# MainBoard.net
KiCad netlist of a schematic drawn in Altium Designer
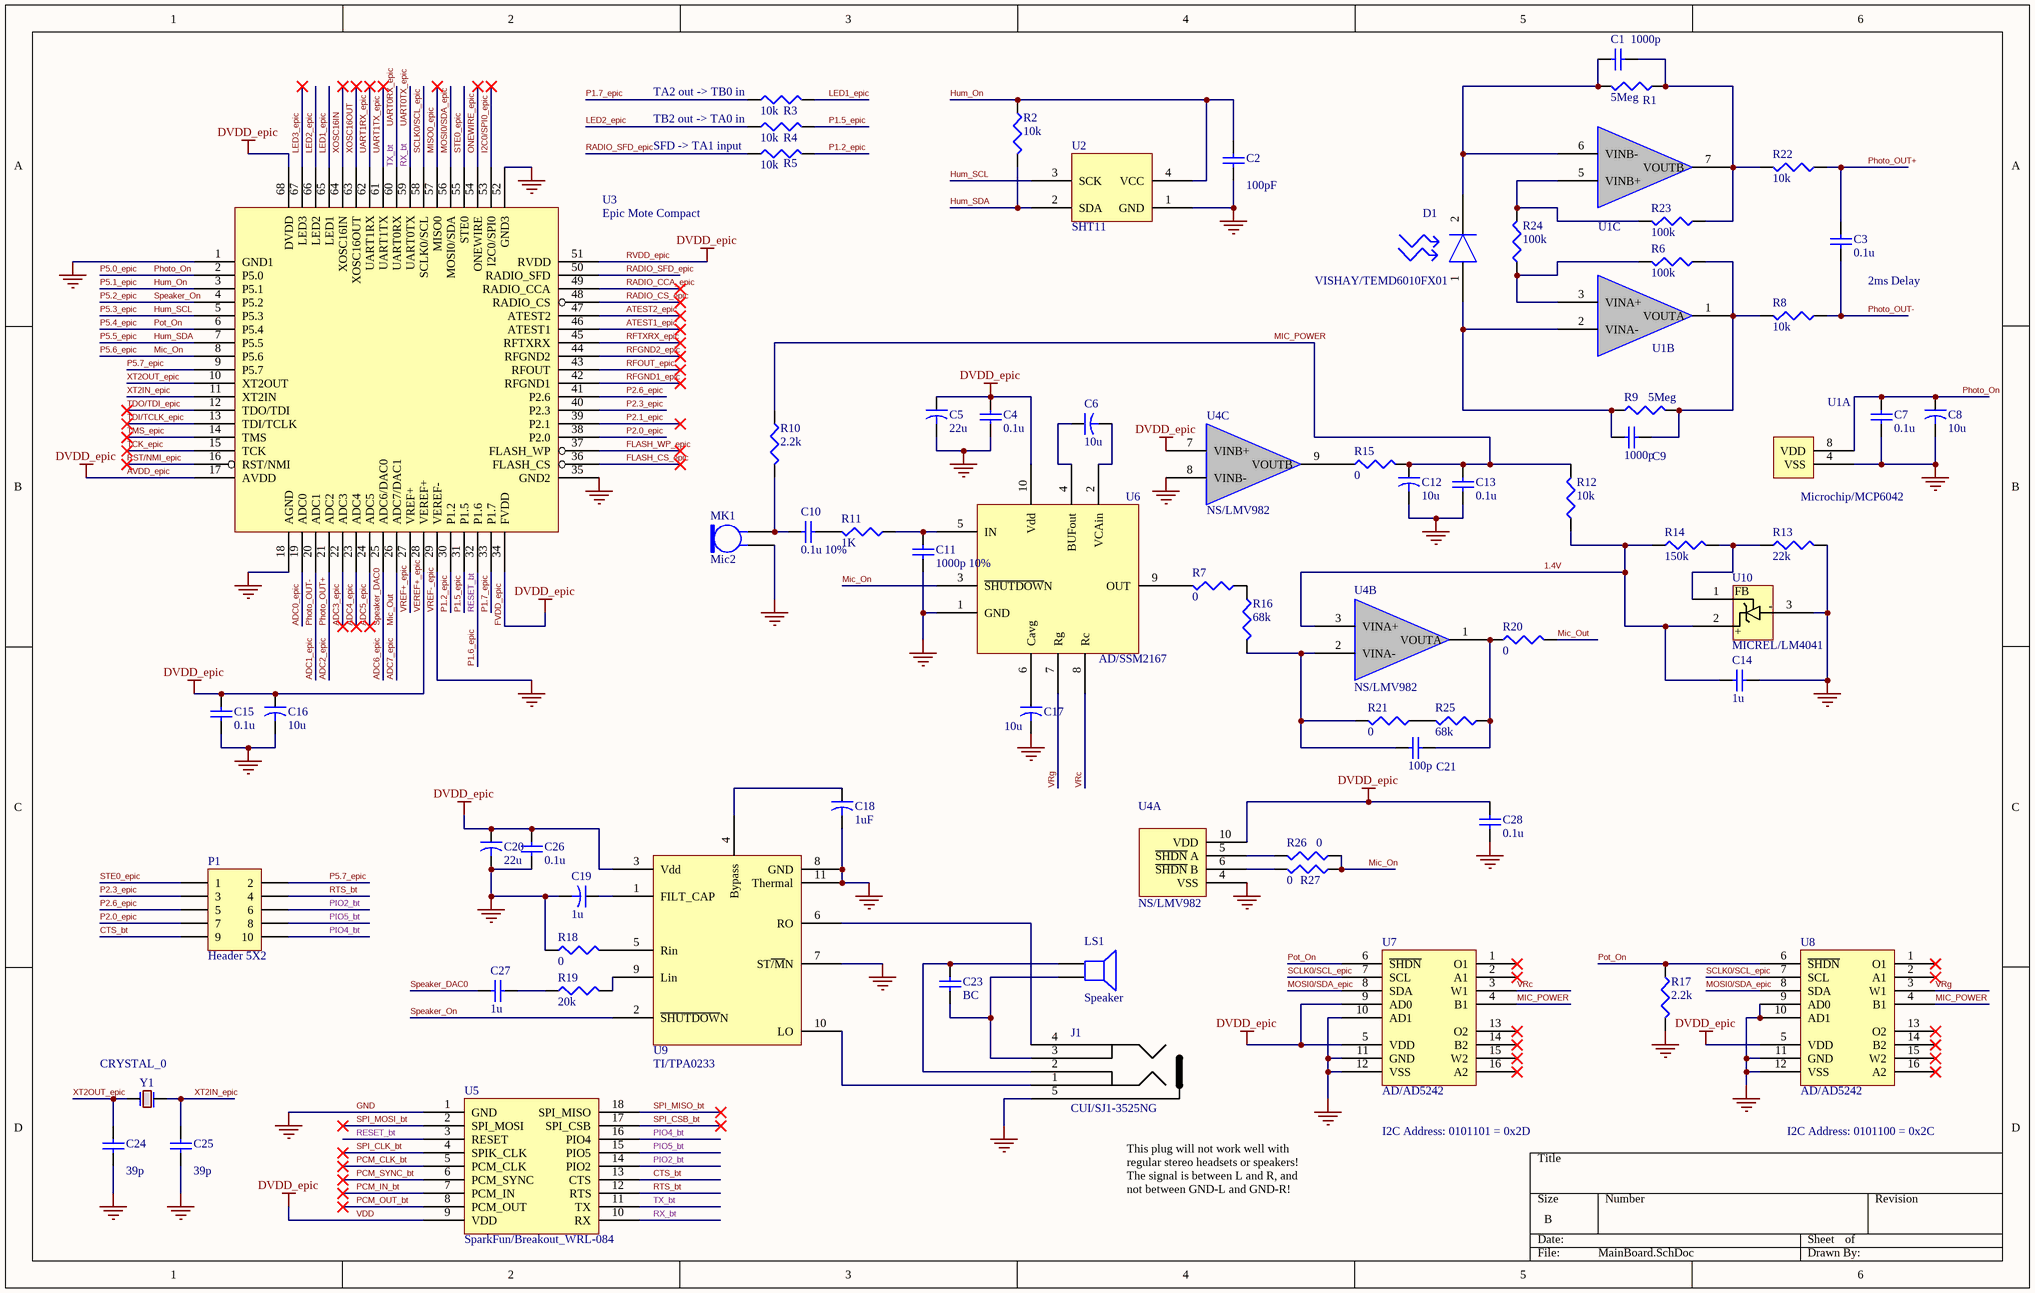
[diagram p0: MainBoard.SchDoc]

(export (version "E")
  (design (tool "Eeschema 10.0.6"))
  (components
    (comp (ref "C1")
      (value "1000p")
      (footprint "CC1608-0603")
      (description "Capacitor")
      (fields (field (name "Comment") "Cap") (field (name "PUBLISHER") "Altium Limited"))
      (libsource (lib "Miscellaneous Devices") (part "Cap"))
    )
    (comp (ref "C2")
      (value "100pF")
      (footprint "CC1608-0603")
      (description "Capacitor")
      (fields (field (name "Comment") "Cap") (field (name "PUBLISHER") "Altium Limited"))
      (libsource (lib "Miscellaneous Devices") (part "Cap"))
    )
    (comp (ref "C3")
      (value "0.1u")
      (footprint "CC1608-0603")
      (description "Capacitor")
      (fields (field (name "Comment") "Cap") (field (name "PUBLISHER") "Altium Limited"))
      (libsource (lib "Miscellaneous Devices") (part "Cap"))
    )
    (comp (ref "C4")
      (value "0.1u")
      (footprint "CC1608-0603")
      (description "Capacitor")
      (fields (field (name "Comment") "Cap") (field (name "PUBLISHER") "Altium Limited"))
      (libsource (lib "Miscellaneous Devices") (part "Cap"))
    )
    (comp (ref "C5")
      (value "22u")
      (footprint "CC3216-1206")
      (description "Capacitor")
      (fields (field (name "Comment") "Cap2") (field (name "PUBLISHER") "Altium Limited"))
      (libsource (lib "") (part "Cap2_1"))
    )
    (comp (ref "C6")
      (value "10u")
      (footprint "CC1608-0603")
      (description "Capacitor")
      (fields (field (name "Comment") "Cap2") (field (name "PUBLISHER") "Altium Limited"))
      (libsource (lib "Miscellaneous Devices") (part "Cap2"))
    )
    (comp (ref "C7")
      (value "0.1u")
      (footprint "CC1608-0603")
      (description "Capacitor")
      (fields (field (name "Comment") "Cap") (field (name "PUBLISHER") "Altium Limited"))
      (libsource (lib "Miscellaneous Devices") (part "Cap"))
    )
    (comp (ref "C8")
      (value "10u")
      (footprint "CC1608-0603")
      (description "Capacitor")
      (fields (field (name "Comment") "Cap2") (field (name "PUBLISHER") "Altium Limited"))
      (libsource (lib "") (part "Cap2_1"))
    )
    (comp (ref "C9")
      (value "1000p")
      (footprint "CC1608-0603")
      (description "Capacitor")
      (fields (field (name "Comment") "Cap") (field (name "PUBLISHER") "Altium Limited"))
      (libsource (lib "Miscellaneous Devices") (part "Cap"))
    )
    (comp (ref "C10")
      (value "0.1u 10%")
      (footprint "CC1608-0603")
      (description "Capacitor")
      (fields (field (name "Comment") "Cap") (field (name "PUBLISHER") "Altium Limited"))
      (libsource (lib "Miscellaneous Devices") (part "Cap"))
    )
    (comp (ref "C11")
      (value "1000p 10%")
      (footprint "CC1608-0603")
      (description "Capacitor")
      (fields (field (name "Comment") "Cap") (field (name "PUBLISHER") "Altium Limited"))
      (libsource (lib "Miscellaneous Devices") (part "Cap"))
    )
    (comp (ref "C12")
      (value "10u")
      (footprint "CC1608-0603")
      (description "Capacitor")
      (fields (field (name "Comment") "Cap2") (field (name "PUBLISHER") "Altium Limited"))
      (libsource (lib "") (part "Cap2_1"))
    )
    (comp (ref "C13")
      (value "0.1u")
      (footprint "CC1608-0603")
      (description "Capacitor")
      (fields (field (name "Comment") "Cap") (field (name "PUBLISHER") "Altium Limited"))
      (libsource (lib "Miscellaneous Devices") (part "Cap"))
    )
    (comp (ref "C14")
      (value "1u")
      (footprint "CC1608-0603")
      (description "Capacitor")
      (fields (field (name "Comment") "Cap") (field (name "PUBLISHER") "Altium Limited"))
      (libsource (lib "") (part "Cap_1"))
    )
    (comp (ref "C15")
      (value "0.1u")
      (footprint "CC1608-0603")
      (description "Capacitor")
      (fields (field (name "Comment") "Cap") (field (name "PUBLISHER") "Altium Limited"))
      (libsource (lib "Miscellaneous Devices") (part "Cap"))
    )
    (comp (ref "C16")
      (value "10u")
      (footprint "CC1608-0603")
      (description "Capacitor")
      (fields (field (name "Comment") "Cap2") (field (name "PUBLISHER") "Altium Limited"))
      (libsource (lib "") (part "Cap2_1"))
    )
    (comp (ref "C17")
      (value "10u")
      (footprint "CC1608-0603")
      (description "Capacitor")
      (fields (field (name "Comment") "Cap2") (field (name "PUBLISHER") "Altium Limited"))
      (libsource (lib "Miscellaneous Devices") (part "Cap2"))
    )
    (comp (ref "C18")
      (value "1uF")
      (footprint "CC1608-0603")
      (description "Capacitor")
      (fields (field (name "Comment") "Cap2") (field (name "PUBLISHER") "Altium Limited"))
      (libsource (lib "Miscellaneous Devices") (part "Cap2"))
    )
    (comp (ref "C19")
      (value "1u")
      (footprint "CC1608-0603")
      (description "Capacitor")
      (fields (field (name "Comment") "Cap2") (field (name "PUBLISHER") "Altium Limited"))
      (libsource (lib "Miscellaneous Devices") (part "Cap2"))
    )
    (comp (ref "C20")
      (value "22u")
      (footprint "CC3216-1206")
      (description "Capacitor")
      (fields (field (name "Comment") "Cap2") (field (name "PUBLISHER") "Altium Limited"))
      (libsource (lib "") (part "Cap2_1"))
    )
    (comp (ref "C21")
      (value "100p")
      (footprint "CC1608-0603")
      (description "Capacitor")
      (fields (field (name "Comment") "Cap") (field (name "PUBLISHER") "Altium Limited"))
      (libsource (lib "Miscellaneous Devices") (part "Cap"))
    )
    (comp (ref "C23")
      (value "BC")
      (footprint "CC1608-0603")
      (description "Capacitor")
      (fields (field (name "Comment") "Cap") (field (name "PUBLISHER") "Altium Limited"))
      (libsource (lib "Miscellaneous Devices") (part "Cap"))
    )
    (comp (ref "C24")
      (value "39p")
      (footprint "CC1608-0603")
      (description "Capacitor")
      (fields (field (name "Comment") "Cap") (field (name "PUBLISHER") "Altium Limited"))
      (libsource (lib "Miscellaneous Devices") (part "Cap"))
    )
    (comp (ref "C25")
      (value "39p")
      (footprint "CC1608-0603")
      (description "Capacitor")
      (fields (field (name "Comment") "Cap") (field (name "PUBLISHER") "Altium Limited"))
      (libsource (lib "Miscellaneous Devices") (part "Cap"))
    )
    (comp (ref "C26")
      (value "0.1u")
      (footprint "CC1608-0603")
      (description "Capacitor")
      (fields (field (name "Comment") "Cap") (field (name "PUBLISHER") "Altium Limited"))
      (libsource (lib "Miscellaneous Devices") (part "Cap"))
    )
    (comp (ref "C27")
      (value "1u")
      (footprint "CC1608-0603")
      (description "Capacitor")
      (fields (field (name "Comment") "Cap") (field (name "PUBLISHER") "Altium Limited"))
      (libsource (lib "Miscellaneous Devices") (part "Cap"))
    )
    (comp (ref "C28")
      (value "0.1u")
      (footprint "CC1608-0603")
      (description "Capacitor")
      (fields (field (name "Comment") "Cap") (field (name "PUBLISHER") "Altium Limited"))
      (libsource (lib "Miscellaneous Devices") (part "Cap"))
    )
    (comp (ref "D1")
      (value "VISHAY/TEMD6010FX01")
      (footprint "VISHAY/TEMD6010FX01")
      (libsource (lib "Schematics") (part "VISHAY/TEMD6010FX01"))
    )
    (comp (ref "J1")
      (value "CUI/SJ1-3525NG")
      (footprint "CUI/PHONE_JACK_3.5mm")
      (libsource (lib "Schematics") (part "CUI/SJ1-3525NG"))
    )
    (comp (ref "LS1")
      (value "Speaker")
      (footprint "PIN2")
      (description "Loudspeaker")
      (fields (field (name "PUBLISHER") "Altium Limited"))
      (libsource (lib "Miscellaneous Devices") (part "Speaker"))
    )
    (comp (ref "MK1")
      (value "Mic2")
      (footprint "PIN2")
      (description "Microphone")
      (fields (field (name "PUBLISHER") "Altium Limited"))
      (libsource (lib "Miscellaneous Devices") (part "Mic2"))
    )
    (comp (ref "P1")
      (value "Header 5X2")
      (footprint "HDR2X5")
      (description "Header, 5-Pin, Dual row")
      (fields (field (name "PUBLISHER") "Altium Limited"))
      (libsource (lib "Miscellaneous Connectors") (part "Header 5X2"))
    )
    (comp (ref "R1")
      (value "5Meg")
      (footprint "CR1608-0603")
      (description "Resistor")
      (fields (field (name "Comment") "Res3") (field (name "PUBLISHER") "Altium Limited"))
      (libsource (lib "Miscellaneous Devices") (part "Res3"))
    )
    (comp (ref "R2")
      (value "10k")
      (footprint "CR1608-0603")
      (description "Resistor")
      (fields (field (name "Comment") "Res3") (field (name "PUBLISHER") "Altium Limited"))
      (libsource (lib "Miscellaneous Devices") (part "Res3"))
    )
    (comp (ref "R3")
      (value "10k")
      (footprint "CR1608-0603")
      (description "Resistor")
      (fields (field (name "Comment") "Res3") (field (name "PUBLISHER") "Altium Limited"))
      (libsource (lib "Miscellaneous Devices") (part "Res3"))
    )
    (comp (ref "R4")
      (value "10k")
      (footprint "CR1608-0603")
      (description "Resistor")
      (fields (field (name "Comment") "Res3") (field (name "PUBLISHER") "Altium Limited"))
      (libsource (lib "Miscellaneous Devices") (part "Res3"))
    )
    (comp (ref "R5")
      (value "10k")
      (footprint "CR1608-0603")
      (description "Resistor")
      (fields (field (name "Comment") "Res3") (field (name "PUBLISHER") "Altium Limited"))
      (libsource (lib "Miscellaneous Devices") (part "Res3"))
    )
    (comp (ref "R6")
      (value "100k")
      (footprint "CR1608-0603")
      (description "Resistor")
      (fields (field (name "Comment") "Res3") (field (name "PUBLISHER") "Altium Limited"))
      (libsource (lib "Miscellaneous Devices") (part "Res3"))
    )
    (comp (ref "R7")
      (value "0")
      (footprint "CR1608-0603")
      (description "Resistor")
      (fields (field (name "Comment") "Res3") (field (name "PUBLISHER") "Altium Limited"))
      (libsource (lib "Miscellaneous Devices") (part "Res3"))
    )
    (comp (ref "R8")
      (value "10k")
      (footprint "CR1608-0603")
      (description "Resistor")
      (fields (field (name "Comment") "Res3") (field (name "PUBLISHER") "Altium Limited"))
      (libsource (lib "Miscellaneous Devices") (part "Res3"))
    )
    (comp (ref "R9")
      (value "5Meg")
      (footprint "CR1608-0603")
      (description "Resistor")
      (fields (field (name "Comment") "Res3") (field (name "PUBLISHER") "Altium Limited"))
      (libsource (lib "Miscellaneous Devices") (part "Res3"))
    )
    (comp (ref "R10")
      (value "2.2k")
      (footprint "CR1608-0603")
      (description "Resistor")
      (fields (field (name "Comment") "Res3") (field (name "PUBLISHER") "Altium Limited"))
      (libsource (lib "Miscellaneous Devices") (part "Res3"))
    )
    (comp (ref "R11")
      (value "1K")
      (footprint "CR1608-0603")
      (description "Resistor")
      (fields (field (name "Comment") "Res3") (field (name "PUBLISHER") "Altium Limited"))
      (libsource (lib "Miscellaneous Devices") (part "Res3"))
    )
    (comp (ref "R12")
      (value "10k")
      (footprint "CR1608-0603")
      (description "Resistor")
      (fields (field (name "Comment") "Res3") (field (name "PUBLISHER") "Altium Limited"))
      (libsource (lib "Miscellaneous Devices") (part "Res3"))
    )
    (comp (ref "R13")
      (value "22k")
      (footprint "CR1608-0603")
      (description "Resistor")
      (fields (field (name "Comment") "Res3") (field (name "PUBLISHER") "Altium Limited"))
      (libsource (lib "Miscellaneous Devices") (part "Res3"))
    )
    (comp (ref "R14")
      (value "150k")
      (footprint "CR1608-0603")
      (description "Resistor")
      (fields (field (name "Comment") "Res3") (field (name "PUBLISHER") "Altium Limited"))
      (libsource (lib "Miscellaneous Devices") (part "Res3"))
    )
    (comp (ref "R15")
      (value "0")
      (footprint "CR1608-0603")
      (description "Resistor")
      (fields (field (name "Comment") "Res3") (field (name "PUBLISHER") "Altium Limited"))
      (libsource (lib "Miscellaneous Devices") (part "Res3"))
    )
    (comp (ref "R16")
      (value "68k")
      (footprint "CR1608-0603")
      (description "Resistor")
      (fields (field (name "Comment") "Res3") (field (name "PUBLISHER") "Altium Limited"))
      (libsource (lib "") (part "Res3_1"))
    )
    (comp (ref "R17")
      (value "2.2k")
      (footprint "CR1608-0603")
      (description "Resistor")
      (fields (field (name "Comment") "Res3") (field (name "PUBLISHER") "Altium Limited"))
      (libsource (lib "Miscellaneous Devices") (part "Res3"))
    )
    (comp (ref "R18")
      (value "0")
      (footprint "CR1608-0603")
      (description "Resistor")
      (fields (field (name "Comment") "Res3") (field (name "PUBLISHER") "Altium Limited"))
      (libsource (lib "Miscellaneous Devices") (part "Res3"))
    )
    (comp (ref "R19")
      (value "20k")
      (footprint "CR1608-0603")
      (description "Resistor")
      (fields (field (name "Comment") "Res3") (field (name "PUBLISHER") "Altium Limited"))
      (libsource (lib "Miscellaneous Devices") (part "Res3"))
    )
    (comp (ref "R20")
      (value "0")
      (footprint "CR1608-0603")
      (description "Resistor")
      (fields (field (name "Comment") "Res3") (field (name "PUBLISHER") "Altium Limited"))
      (libsource (lib "Miscellaneous Devices") (part "Res3"))
    )
    (comp (ref "R21")
      (value "0")
      (footprint "CR1608-0603")
      (description "Resistor")
      (fields (field (name "Comment") "Res3") (field (name "PUBLISHER") "Altium Limited"))
      (libsource (lib "Miscellaneous Devices") (part "Res3"))
    )
    (comp (ref "R22")
      (value "10k")
      (footprint "CR1608-0603")
      (description "Resistor")
      (fields (field (name "Comment") "Res3") (field (name "PUBLISHER") "Altium Limited"))
      (libsource (lib "Miscellaneous Devices") (part "Res3"))
    )
    (comp (ref "R23")
      (value "100k")
      (footprint "CR1608-0603")
      (description "Resistor")
      (fields (field (name "Comment") "Res3") (field (name "PUBLISHER") "Altium Limited"))
      (libsource (lib "Miscellaneous Devices") (part "Res3"))
    )
    (comp (ref "R24")
      (value "100k")
      (footprint "CR1608-0603")
      (description "Resistor")
      (fields (field (name "Comment") "Res3") (field (name "PUBLISHER") "Altium Limited"))
      (libsource (lib "Miscellaneous Devices") (part "Res3"))
    )
    (comp (ref "R25")
      (value "68k")
      (footprint "CR1608-0603")
      (description "Resistor")
      (fields (field (name "Comment") "Res3") (field (name "PUBLISHER") "Altium Limited"))
      (libsource (lib "Miscellaneous Devices") (part "Res3"))
    )
    (comp (ref "R26")
      (value "0")
      (footprint "CR1608-0603")
      (description "Resistor")
      (fields (field (name "Comment") "Res3") (field (name "PUBLISHER") "Altium Limited"))
      (libsource (lib "Miscellaneous Devices") (part "Res3"))
    )
    (comp (ref "R27")
      (value "0")
      (footprint "CR1608-0603")
      (description "Resistor")
      (fields (field (name "Comment") "Res3") (field (name "PUBLISHER") "Altium Limited"))
      (libsource (lib "Miscellaneous Devices") (part "Res3"))
    )
    (comp (ref "U1")
      (value "Microchip/MCP6042")
      (footprint "SOIC127P600X175-8N")
      (libsource (lib "Schematics") (part "Microchip/MCP6042"))
    )
    (comp (ref "U2")
      (value "SHT11")
      (footprint "Sensirion/SHT11")
      (libsource (lib "Schematics") (part "SHT11"))
    )
    (comp (ref "U3")
      (value "Epic Mote Compact")
      (footprint "UCB/Epic_Quanto_Header")
      (libsource (lib "Schematics") (part "Epic Mote Compact"))
    )
    (comp (ref "U4")
      (value "NS/LMV982")
      (footprint "MSOP10")
      (libsource (lib "Schematics") (part "NS/LMV982"))
    )
    (comp (ref "U5")
      (value "SparkFun/Breakout_WRL-084")
      (footprint "SparkFun/Breakout_WRL-084")
      (libsource (lib "Schematics") (part "SparkFun/Breakout_WRL-084"))
    )
    (comp (ref "U6")
      (value "AD/SSM2167")
      (footprint "MSOP127P600-8N")
      (libsource (lib "Schematics") (part "AD/SSM2167"))
    )
    (comp (ref "U7")
      (value "AD/AD5242")
      (footprint "SOIC127P600X175-16N")
      (libsource (lib "Schematics") (part "AD/AD5242"))
    )
    (comp (ref "U8")
      (value "AD/AD5242")
      (footprint "SOIC127P600X175-16N")
      (libsource (lib "Schematics") (part "AD/AD5242"))
    )
    (comp (ref "U9")
      (value "TI/TPA0233")
      (footprint "TSSOP50P480X107_HS-10N")
      (libsource (lib "Schematics") (part "TI/TPA0233"))
    )
    (comp (ref "U10")
      (value "MICREL/LM4041")
      (footprint "SOT231 (M3)")
      (libsource (lib "Schematics") (part "MICREL/LM4041"))
    )
    (comp (ref "Y1")
      (value "CRYSTAL_0")
      (footprint "ECS/CSM-7SSX")
      (libsource (lib "Schematics") (part "CRYSTAL_0"))
    )
  )
  (nets
    (net (code "1") (name "/1.4V") (class "Default")
      (node (ref "C14") (pin "1") (pinfunction "1_1") (pintype "passive"))
      (node (ref "R12") (pin "1") (pinfunction "1_1") (pintype "passive"))
      (node (ref "R14") (pin "1") (pinfunction "1_1") (pintype "passive"))
      (node (ref "U10") (pin "2") (pinfunction "2_2") (pintype "passive"))
      (node (ref "U4") (pin "3") (pinfunction "VINA+_3") (pintype "passive"))
    )
    (net (code "2") (name "/ADC0_epic") (class "Default")
      (node (ref "U3") (pin "19") (pinfunction "ADC0_19") (pintype "passive"))
    )
    (net (code "3") (name "/ADC1_epic") (class "Default")
      (node (ref "C3") (pin "2") (pinfunction "2_2") (pintype "passive"))
      (node (ref "R8") (pin "1") (pinfunction "1_1") (pintype "passive"))
      (node (ref "U3") (pin "20") (pinfunction "ADC1_20") (pintype "passive"))
    )
    (net (code "4") (name "/ADC2_epic") (class "Default")
      (node (ref "C3") (pin "1") (pinfunction "1_1") (pintype "passive"))
      (node (ref "R22") (pin "1") (pinfunction "1_1") (pintype "passive"))
      (node (ref "U3") (pin "21") (pinfunction "ADC2_21") (pintype "passive"))
    )
    (net (code "5") (name "/ADC3_epic") (class "Default")
      (node (ref "U3") (pin "22") (pinfunction "ADC3_22") (pintype "passive+no_connect"))
    )
    (net (code "6") (name "/ADC4_epic") (class "Default")
      (node (ref "U3") (pin "23") (pinfunction "ADC4_23") (pintype "passive+no_connect"))
    )
    (net (code "7") (name "/ADC5_epic") (class "Default")
      (node (ref "U3") (pin "24") (pinfunction "ADC5_24") (pintype "passive+no_connect"))
    )
    (net (code "8") (name "/ADC6_epic") (class "Default")
      (node (ref "C27") (pin "2") (pinfunction "2_2") (pintype "passive"))
      (node (ref "U3") (pin "25") (pinfunction "ADC6/DAC0_25") (pintype "passive"))
    )
    (net (code "9") (name "/ADC7_epic") (class "Default")
      (node (ref "R20") (pin "2") (pinfunction "2_2") (pintype "passive"))
      (node (ref "U3") (pin "26") (pinfunction "ADC7/DAC1_26") (pintype "passive"))
    )
    (net (code "10") (name "/ATEST1_epic") (class "Default")
      (node (ref "U3") (pin "46") (pinfunction "ATEST1_46") (pintype "passive+no_connect"))
    )
    (net (code "11") (name "/ATEST2_epic") (class "Default")
      (node (ref "U3") (pin "47") (pinfunction "ATEST2_47") (pintype "passive+no_connect"))
    )
    (net (code "12") (name "/CTS_bt") (class "Default")
      (node (ref "P1") (pin "9") (pinfunction "9_9") (pintype "passive"))
      (node (ref "U5") (pin "13") (pinfunction "CTS_13") (pintype "passive"))
    )
    (net (code "13") (name "/FLASH_CS_epic") (class "Default")
      (node (ref "U3") (pin "36") (pinfunction "FLASH_CS_36") (pintype "passive+no_connect"))
    )
    (net (code "14") (name "/FLASH_WP_epic") (class "Default")
      (node (ref "U3") (pin "37") (pinfunction "FLASH_WP_37") (pintype "passive+no_connect"))
    )
    (net (code "15") (name "/Hum_On") (class "Default")
      (node (ref "C2") (pin "2") (pinfunction "2_2") (pintype "passive"))
      (node (ref "R2") (pin "1") (pinfunction "1_1") (pintype "passive"))
      (node (ref "U2") (pin "4") (pinfunction "VCC_4") (pintype "power_in"))
      (node (ref "U3") (pin "3") (pinfunction "P5.1_3") (pintype "passive"))
    )
    (net (code "16") (name "/Hum_SCL") (class "Default")
      (node (ref "U2") (pin "3") (pinfunction "SCK_3") (pintype "passive"))
      (node (ref "U3") (pin "5") (pinfunction "P5.3_5") (pintype "passive"))
    )
    (net (code "17") (name "/Hum_SDA") (class "Default")
      (node (ref "R2") (pin "2") (pinfunction "2_2") (pintype "passive"))
      (node (ref "U2") (pin "2") (pinfunction "SDA_2") (pintype "passive"))
      (node (ref "U3") (pin "7") (pinfunction "P5.5_7") (pintype "passive"))
    )
    (net (code "18") (name "/I2C0{slash}SPI0_epic") (class "Default")
      (node (ref "U3") (pin "53") (pinfunction "I2C0/SPI0_53") (pintype "passive+no_connect"))
    )
    (net (code "19") (name "/LED1_epic") (class "Default")
      (node (ref "R3") (pin "2") (pinfunction "2_2") (pintype "passive"))
      (node (ref "U3") (pin "65") (pinfunction "LED1_65") (pintype "passive"))
    )
    (net (code "20") (name "/LED2_epic") (class "Default")
      (node (ref "R4") (pin "1") (pinfunction "1_1") (pintype "passive"))
      (node (ref "U3") (pin "66") (pinfunction "LED2_66") (pintype "passive"))
    )
    (net (code "21") (name "/LED3_epic") (class "Default")
      (node (ref "U3") (pin "67") (pinfunction "LED3_67") (pintype "passive+no_connect"))
    )
    (net (code "22") (name "/MIC_POWER") (class "Default")
      (node (ref "C12") (pin "1") (pinfunction "1_1") (pintype "passive"))
      (node (ref "C13") (pin "1") (pinfunction "1_1") (pintype "passive"))
      (node (ref "R10") (pin "1") (pinfunction "1_1") (pintype "passive"))
      (node (ref "R12") (pin "2") (pinfunction "2_2") (pintype "passive"))
      (node (ref "R15") (pin "2") (pinfunction "2_2") (pintype "passive"))
      (node (ref "U7") (pin "4") (pinfunction "B1_4") (pintype "passive"))
      (node (ref "U8") (pin "4") (pinfunction "B1_4") (pintype "passive"))
    )
    (net (code "23") (name "/MISO0_epic") (class "Default")
      (node (ref "U3") (pin "57") (pinfunction "MISO0_57") (pintype "passive+no_connect"))
    )
    (net (code "24") (name "/MOSI0{slash}SDA_epic") (class "Default")
      (node (ref "U3") (pin "56") (pinfunction "MOSI0/SDA_56") (pintype "passive"))
      (node (ref "U7") (pin "8") (pinfunction "SDA_8") (pintype "passive"))
      (node (ref "U8") (pin "8") (pinfunction "SDA_8") (pintype "passive"))
    )
    (net (code "25") (name "/Mic_On") (class "Default")
      (node (ref "R26") (pin "2") (pinfunction "2_2") (pintype "passive"))
      (node (ref "R27") (pin "2") (pinfunction "2_2") (pintype "passive"))
      (node (ref "U3") (pin "8") (pinfunction "P5.6_8") (pintype "passive"))
      (node (ref "U6") (pin "3") (pinfunction "~{SHUTDOW}N_3") (pintype "passive"))
    )
    (net (code "26") (name "/ONEWIRE_epic") (class "Default")
      (node (ref "U3") (pin "54") (pinfunction "ONEWIRE_54") (pintype "passive+no_connect"))
    )
    (net (code "27") (name "/P1.2_epic") (class "Default")
      (node (ref "R5") (pin "2") (pinfunction "2_2") (pintype "passive"))
      (node (ref "U3") (pin "30") (pinfunction "P1.2_30") (pintype "passive"))
    )
    (net (code "28") (name "/P1.5_epic") (class "Default")
      (node (ref "R4") (pin "2") (pinfunction "2_2") (pintype "passive"))
      (node (ref "U3") (pin "31") (pinfunction "P1.5_31") (pintype "passive"))
    )
    (net (code "29") (name "/P1.6_epic") (class "Default")
      (node (ref "U3") (pin "32") (pinfunction "P1.6_32") (pintype "passive"))
      (node (ref "U5") (pin "3") (pinfunction "RESET_3") (pintype "passive"))
    )
    (net (code "30") (name "/P1.7_epic") (class "Default")
      (node (ref "R3") (pin "1") (pinfunction "1_1") (pintype "passive"))
      (node (ref "U3") (pin "33") (pinfunction "P1.7_33") (pintype "passive"))
    )
    (net (code "31") (name "/P2.0_epic") (class "Default")
      (node (ref "P1") (pin "7") (pinfunction "7_7") (pintype "passive"))
      (node (ref "U3") (pin "38") (pinfunction "P2.0_38") (pintype "passive"))
    )
    (net (code "32") (name "/P2.1_epic") (class "Default")
      (node (ref "U3") (pin "39") (pinfunction "P2.1_39") (pintype "passive+no_connect"))
    )
    (net (code "33") (name "/P2.3_epic") (class "Default")
      (node (ref "P1") (pin "3") (pinfunction "3_3") (pintype "passive"))
      (node (ref "U3") (pin "40") (pinfunction "P2.3_40") (pintype "passive"))
    )
    (net (code "34") (name "/P2.6_epic") (class "Default")
      (node (ref "P1") (pin "5") (pinfunction "5_5") (pintype "passive"))
      (node (ref "U3") (pin "41") (pinfunction "P2.6_41") (pintype "passive"))
    )
    (net (code "35") (name "/P5.0_epic") (class "Default")
      (node (ref "C7") (pin "1") (pinfunction "1_1") (pintype "passive"))
      (node (ref "C8") (pin "1") (pinfunction "1_1") (pintype "passive"))
      (node (ref "U1") (pin "8") (pinfunction "VDD_8") (pintype "power_in"))
      (node (ref "U3") (pin "2") (pinfunction "P5.0_2") (pintype "passive"))
    )
    (net (code "36") (name "/P5.2_epic") (class "Default")
      (node (ref "U3") (pin "4") (pinfunction "P5.2_4") (pintype "passive"))
      (node (ref "U9") (pin "2") (pinfunction "~{SHUTDOW}N_2") (pintype "passive"))
    )
    (net (code "37") (name "/P5.4_epic") (class "Default")
      (node (ref "R17") (pin "1") (pinfunction "1_1") (pintype "passive"))
      (node (ref "U3") (pin "6") (pinfunction "P5.4_6") (pintype "passive"))
      (node (ref "U7") (pin "6") (pinfunction "~{SHDN}_6") (pintype "passive"))
      (node (ref "U8") (pin "6") (pinfunction "~{SHDN}_6") (pintype "passive"))
    )
    (net (code "38") (name "/P5.7_epic") (class "Default")
      (node (ref "P1") (pin "2") (pinfunction "2_2") (pintype "passive"))
      (node (ref "U3") (pin "9") (pinfunction "P5.7_9") (pintype "passive"))
    )
    (net (code "39") (name "/PCM_CLK_bt") (class "Default")
      (node (ref "U5") (pin "5") (pinfunction "PCM_CLK_5") (pintype "passive+no_connect"))
    )
    (net (code "40") (name "/PCM_IN_bt") (class "Default")
      (node (ref "U5") (pin "7") (pinfunction "PCM_IN_7") (pintype "passive+no_connect"))
    )
    (net (code "41") (name "/PCM_OUT_bt") (class "Default")
      (node (ref "U5") (pin "8") (pinfunction "PCM_OUT_8") (pintype "passive+no_connect"))
    )
    (net (code "42") (name "/PCM_SYNC_bt") (class "Default")
      (node (ref "U5") (pin "6") (pinfunction "PCM_SYNC_6") (pintype "passive+no_connect"))
    )
    (net (code "43") (name "/PIO2_bt") (class "Default")
      (node (ref "P1") (pin "6") (pinfunction "6_6") (pintype "passive"))
      (node (ref "U5") (pin "14") (pinfunction "PIO2_14") (pintype "passive"))
    )
    (net (code "44") (name "/PIO4_bt") (class "Default")
      (node (ref "P1") (pin "10") (pinfunction "10_10") (pintype "passive"))
      (node (ref "U5") (pin "16") (pinfunction "PIO4_16") (pintype "passive"))
    )
    (net (code "45") (name "/PIO5_bt") (class "Default")
      (node (ref "P1") (pin "8") (pinfunction "8_8") (pintype "passive"))
      (node (ref "U5") (pin "15") (pinfunction "PIO5_15") (pintype "passive"))
    )
    (net (code "46") (name "/RADIO_CCA_epic") (class "Default")
      (node (ref "U3") (pin "49") (pinfunction "RADIO_CCA_49") (pintype "passive+no_connect"))
    )
    (net (code "47") (name "/RADIO_CS_epic") (class "Default")
      (node (ref "U3") (pin "48") (pinfunction "RADIO_CS_48") (pintype "passive+no_connect"))
    )
    (net (code "48") (name "/RADIO_SFD_epic") (class "Default")
      (node (ref "R5") (pin "1") (pinfunction "1_1") (pintype "passive"))
      (node (ref "U3") (pin "50") (pinfunction "RADIO_SFD_50") (pintype "passive"))
    )
    (net (code "49") (name "/RFGND1_epic") (class "Default")
      (node (ref "U3") (pin "42") (pinfunction "RFGND1_42") (pintype "passive+no_connect"))
    )
    (net (code "50") (name "/RFGND2_epic") (class "Default")
      (node (ref "U3") (pin "44") (pinfunction "RFGND2_44") (pintype "passive+no_connect"))
    )
    (net (code "51") (name "/RFOUT_epic") (class "Default")
      (node (ref "U3") (pin "43") (pinfunction "RFOUT_43") (pintype "passive+no_connect"))
    )
    (net (code "52") (name "/RFTXRX_epic") (class "Default")
      (node (ref "U3") (pin "45") (pinfunction "RFTXRX_45") (pintype "passive+no_connect"))
    )
    (net (code "53") (name "/RST{slash}NMI_epic") (class "Default")
      (node (ref "U3") (pin "16") (pinfunction "RST/NMI_16") (pintype "passive+no_connect"))
    )
    (net (code "54") (name "/RTS_bt") (class "Default")
      (node (ref "P1") (pin "4") (pinfunction "4_4") (pintype "passive"))
      (node (ref "U5") (pin "12") (pinfunction "RTS_12") (pintype "passive"))
    )
    (net (code "55") (name "/RX_bt") (class "Default")
      (node (ref "U3") (pin "59") (pinfunction "UART0TX_59") (pintype "passive"))
      (node (ref "U5") (pin "10") (pinfunction "RX_10") (pintype "passive"))
    )
    (net (code "56") (name "/SCLK0{slash}SCL_epic") (class "Default")
      (node (ref "U3") (pin "58") (pinfunction "SCLK0/SCL_58") (pintype "passive"))
      (node (ref "U7") (pin "7") (pinfunction "SCL_7") (pintype "passive"))
      (node (ref "U8") (pin "7") (pinfunction "SCL_7") (pintype "passive"))
    )
    (net (code "57") (name "/SPI_CLK_bt") (class "Default")
      (node (ref "U5") (pin "4") (pinfunction "SPIK_CLK_4") (pintype "passive+no_connect"))
    )
    (net (code "58") (name "/SPI_CSB_bt") (class "Default")
      (node (ref "U5") (pin "17") (pinfunction "SPI_CSB_17") (pintype "passive+no_connect"))
    )
    (net (code "59") (name "/SPI_MISO_bt") (class "Default")
      (node (ref "U5") (pin "18") (pinfunction "SPI_MISO_18") (pintype "passive+no_connect"))
    )
    (net (code "60") (name "/SPI_MOSI_bt") (class "Default")
      (node (ref "U5") (pin "2") (pinfunction "SPI_MOSI_2") (pintype "passive+no_connect"))
    )
    (net (code "61") (name "/STE0_epic") (class "Default")
      (node (ref "P1") (pin "1") (pinfunction "1_1") (pintype "passive"))
      (node (ref "U3") (pin "55") (pinfunction "STE0_55") (pintype "passive"))
    )
    (net (code "62") (name "/TCK_epic") (class "Default")
      (node (ref "U3") (pin "15") (pinfunction "TCK_15") (pintype "passive+no_connect"))
    )
    (net (code "63") (name "/TDI{slash}TCLK_epic") (class "Default")
      (node (ref "U3") (pin "13") (pinfunction "TDI/TCLK_13") (pintype "passive+no_connect"))
    )
    (net (code "64") (name "/TDO{slash}TDI_epic") (class "Default")
      (node (ref "U3") (pin "12") (pinfunction "TDO/TDI_12") (pintype "passive+no_connect"))
    )
    (net (code "65") (name "/TMS_epic") (class "Default")
      (node (ref "U3") (pin "14") (pinfunction "TMS_14") (pintype "passive+no_connect"))
    )
    (net (code "66") (name "/TX_bt") (class "Default")
      (node (ref "U3") (pin "60") (pinfunction "UART0RX_60") (pintype "passive"))
      (node (ref "U5") (pin "11") (pinfunction "TX_11") (pintype "passive"))
    )
    (net (code "67") (name "/UART1RX_epic") (class "Default")
      (node (ref "U3") (pin "62") (pinfunction "UART1RX_62") (pintype "passive+no_connect"))
    )
    (net (code "68") (name "/UART1TX_epic") (class "Default")
      (node (ref "U3") (pin "61") (pinfunction "UART1TX_61") (pintype "passive+no_connect"))
    )
    (net (code "69") (name "/VREF+_epic") (class "Default")
      (node (ref "U3") (pin "27") (pinfunction "VREF+_27") (pintype "passive"))
    )
    (net (code "70") (name "/VRc") (class "Default")
      (node (ref "U6") (pin "8") (pinfunction "Rc_8") (pintype "passive"))
      (node (ref "U7") (pin "3") (pinfunction "W1_3") (pintype "passive"))
    )
    (net (code "71") (name "/VRg") (class "Default")
      (node (ref "U6") (pin "7") (pinfunction "Rg_7") (pintype "passive"))
      (node (ref "U8") (pin "3") (pinfunction "W1_3") (pintype "passive"))
    )
    (net (code "72") (name "/XOSC16IN") (class "Default")
      (node (ref "U3") (pin "64") (pinfunction "XOSC16IN_64") (pintype "passive+no_connect"))
    )
    (net (code "73") (name "/XOSC16OUT") (class "Default")
      (node (ref "U3") (pin "63") (pinfunction "XOSC16OUT_63") (pintype "passive+no_connect"))
    )
    (net (code "74") (name "/XT2IN_epic") (class "Default")
      (node (ref "C25") (pin "2") (pinfunction "2_2") (pintype "passive"))
      (node (ref "U3") (pin "11") (pinfunction "XT2IN_11") (pintype "passive"))
      (node (ref "Y1") (pin "2") (pinfunction "2_2") (pintype "passive"))
    )
    (net (code "75") (name "/XT2OUT_epic") (class "Default")
      (node (ref "C24") (pin "2") (pinfunction "2_2") (pintype "passive"))
      (node (ref "U3") (pin "10") (pinfunction "XT2OUT_10") (pintype "passive"))
      (node (ref "Y1") (pin "1") (pinfunction "1_1") (pintype "passive"))
    )
    (net (code "76") (name "DVDD_epic") (class "Default")
      (node (ref "C15") (pin "1") (pinfunction "1_1") (pintype "passive"))
      (node (ref "C16") (pin "1") (pinfunction "1_1") (pintype "passive"))
      (node (ref "C20") (pin "1") (pinfunction "1_1") (pintype "passive"))
      (node (ref "C26") (pin "1") (pinfunction "1_1") (pintype "passive"))
      (node (ref "C28") (pin "1") (pinfunction "1_1") (pintype "passive"))
      (node (ref "C4") (pin "1") (pinfunction "1_1") (pintype "passive"))
      (node (ref "C5") (pin "1") (pinfunction "1_1") (pintype "passive"))
      (node (ref "U3") (pin "17") (pinfunction "AVDD_17") (pintype "passive"))
      (node (ref "U3") (pin "28") (pinfunction "VEREF+_28") (pintype "passive"))
      (node (ref "U3") (pin "34") (pinfunction "FVDD_34") (pintype "passive"))
      (node (ref "U3") (pin "51") (pinfunction "RVDD_51") (pintype "passive"))
      (node (ref "U3") (pin "68") (pinfunction "DVDD_68") (pintype "passive"))
      (node (ref "U4") (pin "10") (pinfunction "VDD_10") (pintype "power_in"))
      (node (ref "U4") (pin "7") (pinfunction "VINB+_7") (pintype "passive"))
      (node (ref "U5") (pin "9") (pinfunction "VDD_9") (pintype "passive"))
      (node (ref "U6") (pin "10") (pinfunction "Vdd_10") (pintype "passive"))
      (node (ref "U7") (pin "5") (pinfunction "VDD_5") (pintype "passive"))
      (node (ref "U7") (pin "9") (pinfunction "AD0_9") (pintype "passive"))
      (node (ref "U8") (pin "5") (pinfunction "VDD_5") (pintype "passive"))
      (node (ref "U9") (pin "3") (pinfunction "Vdd_3") (pintype "passive"))
    )
    (net (code "77") (name "GND") (class "Default")
      (node (ref "C11") (pin "2") (pinfunction "2_2") (pintype "passive"))
      (node (ref "C12") (pin "2") (pinfunction "2_2") (pintype "passive"))
      (node (ref "C13") (pin "2") (pinfunction "2_2") (pintype "passive"))
      (node (ref "C14") (pin "2") (pinfunction "2_2") (pintype "passive"))
      (node (ref "C15") (pin "2") (pinfunction "2_2") (pintype "passive"))
      (node (ref "C16") (pin "2") (pinfunction "2_2") (pintype "passive"))
      (node (ref "C17") (pin "2") (pinfunction "2_2") (pintype "passive"))
      (node (ref "C18") (pin "2") (pinfunction "2_2") (pintype "passive"))
      (node (ref "C19") (pin "2") (pinfunction "2_2") (pintype "passive"))
      (node (ref "C2") (pin "1") (pinfunction "1_1") (pintype "passive"))
      (node (ref "C20") (pin "2") (pinfunction "2_2") (pintype "passive"))
      (node (ref "C24") (pin "1") (pinfunction "1_1") (pintype "passive"))
      (node (ref "C25") (pin "1") (pinfunction "1_1") (pintype "passive"))
      (node (ref "C26") (pin "2") (pinfunction "2_2") (pintype "passive"))
      (node (ref "C28") (pin "2") (pinfunction "2_2") (pintype "passive"))
      (node (ref "C4") (pin "2") (pinfunction "2_2") (pintype "passive"))
      (node (ref "C5") (pin "2") (pinfunction "2_2") (pintype "passive"))
      (node (ref "C7") (pin "2") (pinfunction "2_2") (pintype "passive"))
      (node (ref "C8") (pin "2") (pinfunction "2_2") (pintype "passive"))
      (node (ref "J1") (pin "5") (pinfunction "5_5") (pintype "passive"))
      (node (ref "MK1") (pin "1") (pinfunction "1_1") (pintype "passive"))
      (node (ref "R13") (pin "2") (pinfunction "2_2") (pintype "passive"))
      (node (ref "R17") (pin "2") (pinfunction "2_2") (pintype "passive"))
      (node (ref "R18") (pin "1") (pinfunction "1_1") (pintype "passive"))
      (node (ref "U1") (pin "4") (pinfunction "VSS_4") (pintype "power_in"))
      (node (ref "U10") (pin "3") (pinfunction "-_3") (pintype "passive"))
      (node (ref "U2") (pin "1") (pinfunction "GND_1") (pintype "power_in"))
      (node (ref "U3") (pin "1") (pinfunction "GND1_1") (pintype "passive"))
      (node (ref "U3") (pin "18") (pinfunction "AGND_18") (pintype "passive"))
      (node (ref "U3") (pin "29") (pinfunction "VEREF-_29") (pintype "passive"))
      (node (ref "U3") (pin "35") (pinfunction "GND2_35") (pintype "passive"))
      (node (ref "U3") (pin "52") (pinfunction "GND3_52") (pintype "passive"))
      (node (ref "U4") (pin "4") (pinfunction "VSS_4") (pintype "power_in"))
      (node (ref "U4") (pin "8") (pinfunction "VINB-_8") (pintype "passive"))
      (node (ref "U5") (pin "1") (pinfunction "GND_1") (pintype "passive"))
      (node (ref "U6") (pin "1") (pinfunction "GND_1") (pintype "passive"))
      (node (ref "U7") (pin "10") (pinfunction "AD1_10") (pintype "passive"))
      (node (ref "U7") (pin "11") (pinfunction "GND_11") (pintype "passive"))
      (node (ref "U7") (pin "12") (pinfunction "VSS_12") (pintype "passive"))
      (node (ref "U8") (pin "10") (pinfunction "AD1_10") (pintype "passive"))
      (node (ref "U8") (pin "11") (pinfunction "GND_11") (pintype "passive"))
      (node (ref "U8") (pin "12") (pinfunction "VSS_12") (pintype "passive"))
      (node (ref "U8") (pin "9") (pinfunction "AD0_9") (pintype "passive"))
      (node (ref "U9") (pin "11") (pinfunction "Thermal_11") (pintype "passive"))
      (node (ref "U9") (pin "7") (pinfunction "ST~{/M}N_7") (pintype "passive"))
      (node (ref "U9") (pin "8") (pinfunction "GND_8") (pintype "passive"))
    )
    (net (code "78") (name "Net-(C10-Pad1)") (class "Default")
      (node (ref "C10") (pin "1") (pinfunction "1_1") (pintype "passive"))
      (node (ref "R11") (pin "2") (pinfunction "2_2") (pintype "passive"))
    )
    (net (code "79") (name "Net-(C10-Pad2)") (class "Default")
      (node (ref "C10") (pin "2") (pinfunction "2_2") (pintype "passive"))
      (node (ref "MK1") (pin "2") (pinfunction "2_2") (pintype "passive"))
      (node (ref "R10") (pin "2") (pinfunction "2_2") (pintype "passive"))
    )
    (net (code "80") (name "Net-(C23-Pad1)") (class "Default")
      (node (ref "C23") (pin "1") (pinfunction "1_1") (pintype "passive"))
      (node (ref "J1") (pin "2") (pinfunction "2_2") (pintype "passive"))
      (node (ref "LS1") (pin "1") (pinfunction "1_1") (pintype "passive"))
    )
    (net (code "81") (name "Net-(C23-Pad2)") (class "Default")
      (node (ref "C23") (pin "2") (pinfunction "2_2") (pintype "passive"))
      (node (ref "J1") (pin "3") (pinfunction "3_3") (pintype "passive"))
      (node (ref "LS1") (pin "2") (pinfunction "2_2") (pintype "passive"))
    )
    (net (code "82") (name "Net-(C27-Pad1)") (class "Default")
      (node (ref "C27") (pin "1") (pinfunction "1_1") (pintype "passive"))
      (node (ref "R19") (pin "1") (pinfunction "1_1") (pintype "passive"))
    )
    (net (code "83") (name "Net-(R13-Pad1)") (class "Default")
      (node (ref "R13") (pin "1") (pinfunction "1_1") (pintype "passive"))
      (node (ref "R14") (pin "2") (pinfunction "2_2") (pintype "passive"))
      (node (ref "U10") (pin "1") (pinfunction "1_1") (pintype "passive"))
    )
    (net (code "84") (name "Net-(R16-Pad2)") (class "Default")
      (node (ref "R16") (pin "2") (pinfunction "2_2") (pintype "passive"))
      (node (ref "R7") (pin "2") (pinfunction "2_2") (pintype "passive"))
    )
    (net (code "85") (name "Net-(R21-Pad2)") (class "Default")
      (node (ref "R21") (pin "2") (pinfunction "2_2") (pintype "passive"))
      (node (ref "R25") (pin "1") (pinfunction "1_1") (pintype "passive"))
    )
    (net (code "86") (name "Net-(U1B-VINA+)") (class "Default")
      (node (ref "R24") (pin "1") (pinfunction "1_1") (pintype "passive"))
      (node (ref "R6") (pin "2") (pinfunction "2_2") (pintype "passive"))
      (node (ref "U1") (pin "3") (pinfunction "VINA+_3") (pintype "passive"))
    )
    (net (code "87") (name "Net-(U1B-VINA-)") (class "Default")
      (node (ref "C9") (pin "2") (pinfunction "2_2") (pintype "passive"))
      (node (ref "D1") (pin "1") (pinfunction "1_1") (pintype "passive"))
      (node (ref "R9") (pin "1") (pinfunction "1_1") (pintype "passive"))
      (node (ref "U1") (pin "2") (pinfunction "VINA-_2") (pintype "passive"))
    )
    (net (code "88") (name "Net-(U1B-VOUTA)") (class "Default")
      (node (ref "C9") (pin "1") (pinfunction "1_1") (pintype "passive"))
      (node (ref "R6") (pin "1") (pinfunction "1_1") (pintype "passive"))
      (node (ref "R8") (pin "2") (pinfunction "2_2") (pintype "passive"))
      (node (ref "R9") (pin "2") (pinfunction "2_2") (pintype "passive"))
      (node (ref "U1") (pin "1") (pinfunction "VOUTA_1") (pintype "passive"))
    )
    (net (code "89") (name "Net-(U1C-VINB+)") (class "Default")
      (node (ref "R23") (pin "2") (pinfunction "2_2") (pintype "passive"))
      (node (ref "R24") (pin "2") (pinfunction "2_2") (pintype "passive"))
      (node (ref "U1") (pin "5") (pinfunction "VINB+_5") (pintype "passive"))
    )
    (net (code "90") (name "Net-(U1C-VINB-)") (class "Default")
      (node (ref "C1") (pin "2") (pinfunction "2_2") (pintype "passive"))
      (node (ref "D1") (pin "2") (pinfunction "2_2") (pintype "passive"))
      (node (ref "R1") (pin "1") (pinfunction "1_1") (pintype "passive"))
      (node (ref "U1") (pin "6") (pinfunction "VINB-_6") (pintype "passive"))
    )
    (net (code "91") (name "Net-(U1C-VOUTB)") (class "Default")
      (node (ref "C1") (pin "1") (pinfunction "1_1") (pintype "passive"))
      (node (ref "R1") (pin "2") (pinfunction "2_2") (pintype "passive"))
      (node (ref "R22") (pin "2") (pinfunction "2_2") (pintype "passive"))
      (node (ref "R23") (pin "1") (pinfunction "1_1") (pintype "passive"))
      (node (ref "U1") (pin "7") (pinfunction "VOUTB_7") (pintype "passive"))
    )
    (net (code "92") (name "Net-(U4A-~{SHDN}_A)") (class "Default")
      (node (ref "R26") (pin "1") (pinfunction "1_1") (pintype "passive"))
      (node (ref "U4") (pin "5") (pinfunction "~{SHDN}_A_5") (pintype "passive"))
    )
    (net (code "93") (name "Net-(U4A-~{SHDN}_B)") (class "Default")
      (node (ref "R27") (pin "1") (pinfunction "1_1") (pintype "passive"))
      (node (ref "U4") (pin "6") (pinfunction "~{SHDN}_B_6") (pintype "passive"))
    )
    (net (code "94") (name "Net-(U4B-VINA-)") (class "Default")
      (node (ref "C21") (pin "2") (pinfunction "2_2") (pintype "passive"))
      (node (ref "R16") (pin "1") (pinfunction "1_1") (pintype "passive"))
      (node (ref "R21") (pin "1") (pinfunction "1_1") (pintype "passive"))
      (node (ref "U4") (pin "2") (pinfunction "VINA-_2") (pintype "passive"))
    )
    (net (code "95") (name "Net-(U4B-VOUTA)") (class "Default")
      (node (ref "C21") (pin "1") (pinfunction "1_1") (pintype "passive"))
      (node (ref "R20") (pin "1") (pinfunction "1_1") (pintype "passive"))
      (node (ref "R25") (pin "2") (pinfunction "2_2") (pintype "passive"))
      (node (ref "U4") (pin "1") (pinfunction "VOUTA_1") (pintype "passive"))
    )
    (net (code "96") (name "Net-(U4C-VOUTB)") (class "Default")
      (node (ref "R15") (pin "1") (pinfunction "1_1") (pintype "passive"))
      (node (ref "U4") (pin "9") (pinfunction "VOUTB_9") (pintype "passive"))
    )
    (net (code "97") (name "Net-(U6-BUFout)") (class "Default")
      (node (ref "C6") (pin "1") (pinfunction "1_1") (pintype "passive"))
      (node (ref "U6") (pin "4") (pinfunction "BUFout_4") (pintype "passive"))
    )
    (net (code "98") (name "Net-(U6-Cavg)") (class "Default")
      (node (ref "C17") (pin "1") (pinfunction "1_1") (pintype "passive"))
      (node (ref "U6") (pin "6") (pinfunction "Cavg_6") (pintype "passive"))
    )
    (net (code "99") (name "Net-(U6-IN)") (class "Default")
      (node (ref "C11") (pin "1") (pinfunction "1_1") (pintype "passive"))
      (node (ref "R11") (pin "1") (pinfunction "1_1") (pintype "passive"))
      (node (ref "U6") (pin "5") (pinfunction "IN_5") (pintype "passive"))
    )
    (net (code "100") (name "Net-(U6-OUT)") (class "Default")
      (node (ref "R7") (pin "1") (pinfunction "1_1") (pintype "passive"))
      (node (ref "U6") (pin "9") (pinfunction "OUT_9") (pintype "passive"))
    )
    (net (code "101") (name "Net-(U6-VCAin)") (class "Default")
      (node (ref "C6") (pin "2") (pinfunction "2_2") (pintype "passive"))
      (node (ref "U6") (pin "2") (pinfunction "VCAin_2") (pintype "passive"))
    )
    (net (code "102") (name "Net-(U9-Bypass)") (class "Default")
      (node (ref "C18") (pin "1") (pinfunction "1_1") (pintype "passive"))
      (node (ref "U9") (pin "4") (pinfunction "Bypass_4") (pintype "passive"))
    )
    (net (code "103") (name "Net-(U9-FILT_CAP)") (class "Default")
      (node (ref "C19") (pin "1") (pinfunction "1_1") (pintype "passive"))
      (node (ref "U9") (pin "1") (pinfunction "FILT_CAP_1") (pintype "passive"))
    )
    (net (code "104") (name "Net-(U9-LO)") (class "Default")
      (node (ref "J1") (pin "1") (pinfunction "1_1") (pintype "passive"))
      (node (ref "U9") (pin "10") (pinfunction "LO_10") (pintype "passive"))
    )
    (net (code "105") (name "Net-(U9-Lin)") (class "Default")
      (node (ref "R19") (pin "2") (pinfunction "2_2") (pintype "passive"))
      (node (ref "U9") (pin "9") (pinfunction "Lin_9") (pintype "passive"))
    )
    (net (code "106") (name "Net-(U9-RO)") (class "Default")
      (node (ref "J1") (pin "4") (pinfunction "4_4") (pintype "passive"))
      (node (ref "U9") (pin "6") (pinfunction "RO_6") (pintype "passive"))
    )
    (net (code "107") (name "Net-(U9-Rin)") (class "Default")
      (node (ref "R18") (pin "2") (pinfunction "2_2") (pintype "passive"))
      (node (ref "U9") (pin "5") (pinfunction "Rin_5") (pintype "passive"))
    )
    (net (code "108") (name "unconnected-(U7-A1-Pad2)") (class "Default")
      (node (ref "U7") (pin "2") (pinfunction "A1_2") (pintype "passive+no_connect"))
    )
    (net (code "109") (name "unconnected-(U7-A2-Pad16)") (class "Default")
      (node (ref "U7") (pin "16") (pinfunction "A2_16") (pintype "passive+no_connect"))
    )
    (net (code "110") (name "unconnected-(U7-B2-Pad14)") (class "Default")
      (node (ref "U7") (pin "14") (pinfunction "B2_14") (pintype "passive+no_connect"))
    )
    (net (code "111") (name "unconnected-(U7-O1-Pad1)") (class "Default")
      (node (ref "U7") (pin "1") (pinfunction "O1_1") (pintype "passive+no_connect"))
    )
    (net (code "112") (name "unconnected-(U7-O2-Pad13)") (class "Default")
      (node (ref "U7") (pin "13") (pinfunction "O2_13") (pintype "passive+no_connect"))
    )
    (net (code "113") (name "unconnected-(U7-W2-Pad15)") (class "Default")
      (node (ref "U7") (pin "15") (pinfunction "W2_15") (pintype "passive+no_connect"))
    )
    (net (code "114") (name "unconnected-(U8-A1-Pad2)") (class "Default")
      (node (ref "U8") (pin "2") (pinfunction "A1_2") (pintype "passive+no_connect"))
    )
    (net (code "115") (name "unconnected-(U8-A2-Pad16)") (class "Default")
      (node (ref "U8") (pin "16") (pinfunction "A2_16") (pintype "passive+no_connect"))
    )
    (net (code "116") (name "unconnected-(U8-B2-Pad14)") (class "Default")
      (node (ref "U8") (pin "14") (pinfunction "B2_14") (pintype "passive+no_connect"))
    )
    (net (code "117") (name "unconnected-(U8-O1-Pad1)") (class "Default")
      (node (ref "U8") (pin "1") (pinfunction "O1_1") (pintype "passive+no_connect"))
    )
    (net (code "118") (name "unconnected-(U8-O2-Pad13)") (class "Default")
      (node (ref "U8") (pin "13") (pinfunction "O2_13") (pintype "passive+no_connect"))
    )
    (net (code "119") (name "unconnected-(U8-W2-Pad15)") (class "Default")
      (node (ref "U8") (pin "15") (pinfunction "W2_15") (pintype "passive+no_connect"))
    )
  )
)
